# Power_Management.net
KiCad netlist of a schematic drawn in Altium Designer
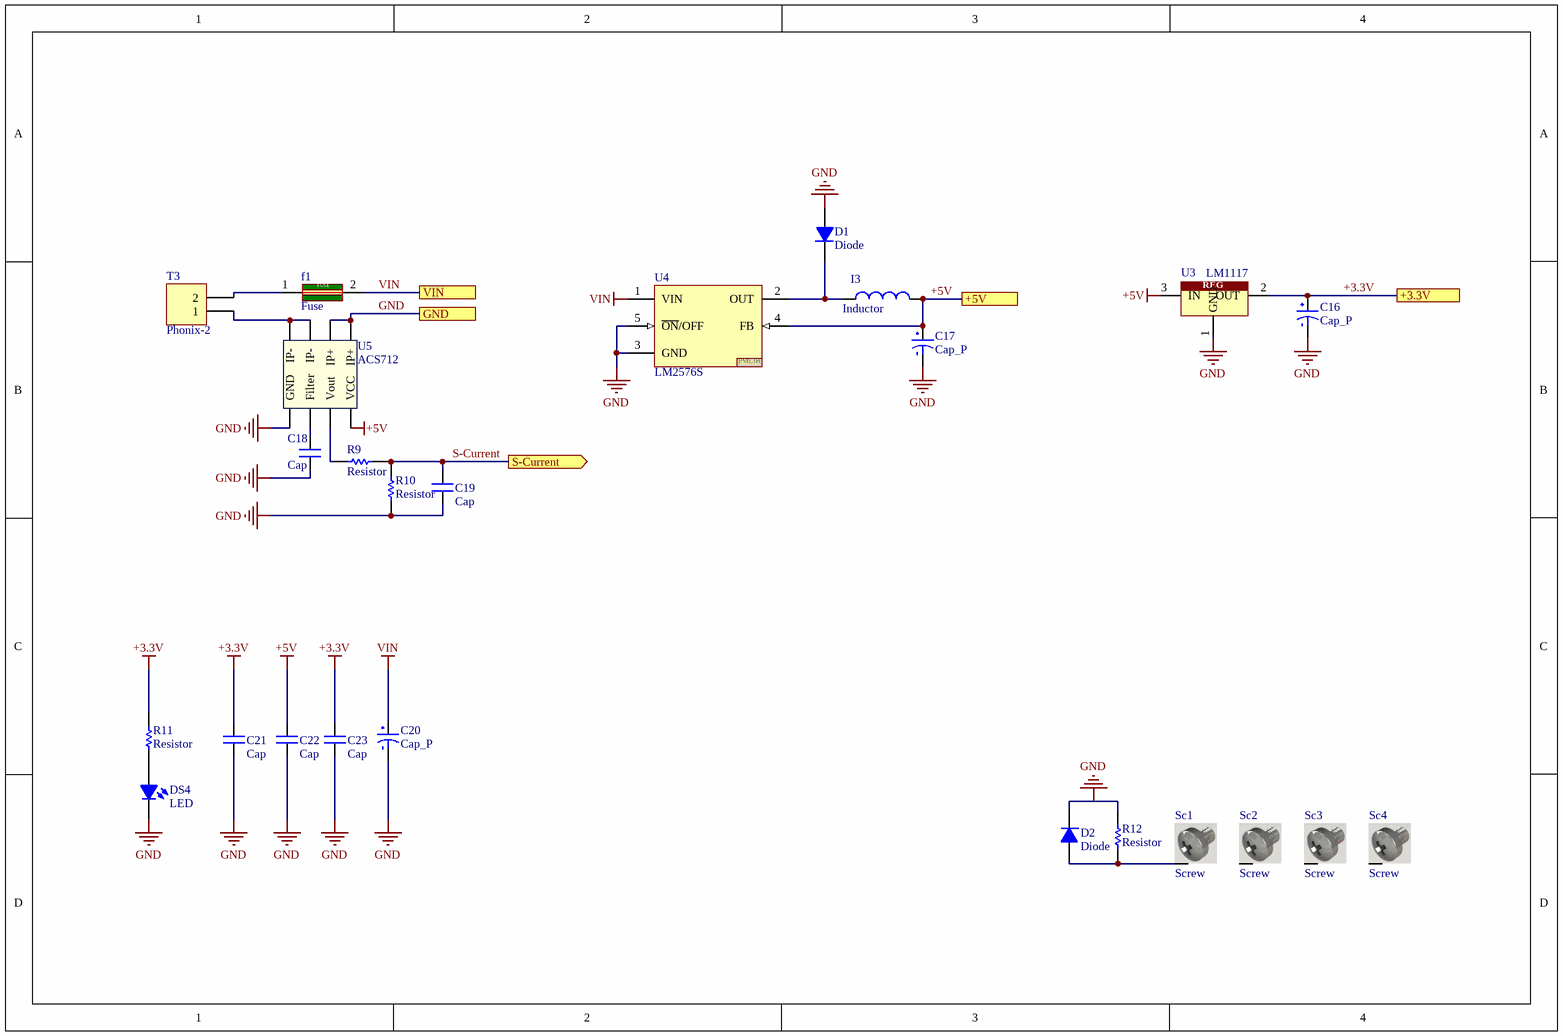
[diagram p0: Power Management.SchDoc]

(export (version "E")
  (design (tool "Eeschema 10.0.6"))
  (components
    (comp (ref "C16")
      (value "Cap_P")
      (footprint "Cap_4mm")
      (description "Polarity")
      (libsource (lib "PMLIB2020") (part "Cap_P"))
    )
    (comp (ref "C17")
      (value "Cap_P")
      (footprint "Cap_4mm")
      (description "Polarity")
      (libsource (lib "PMLIB2020") (part "Cap_P"))
    )
    (comp (ref "C18")
      (value "Cap")
      (footprint "Cap0805")
      (description "Surface mount Capacitor")
      (libsource (lib "PMLIB2020") (part "Cap"))
    )
    (comp (ref "C19")
      (value "Cap")
      (footprint "Cap0805")
      (description "Surface mount Capacitor")
      (libsource (lib "PMLIB2020") (part "Cap"))
    )
    (comp (ref "C20")
      (value "Cap_P")
      (footprint "Cap_5mm")
      (description "Polarity")
      (libsource (lib "PMLIB2020") (part "Cap_P"))
    )
    (comp (ref "C21")
      (value "Cap")
      (footprint "Cap0805")
      (description "Surface mount Capacitor")
      (libsource (lib "PMLIB2020") (part "Cap"))
    )
    (comp (ref "C22")
      (value "Cap")
      (footprint "Cap0805")
      (description "Surface mount Capacitor")
      (libsource (lib "PMLIB2020") (part "Cap"))
    )
    (comp (ref "C23")
      (value "Cap")
      (footprint "Cap0805")
      (description "Surface mount Capacitor")
      (libsource (lib "PMLIB2020") (part "Cap"))
    )
    (comp (ref "D1") (value "Diode") (footprint "Diod-1A-SMD") (libsource (lib "PMLIB2020") (part "Diode")))
    (comp (ref "D2") (value "Diode") (footprint "Diod-1A-SMD") (libsource (lib "PMLIB2020") (part "Diode")))
    (comp (ref "DS4") (value "LED") (footprint "Led0805") (libsource (lib "PMLIB2020") (part "LED")))
    (comp (ref "f1") (value "Fuse") (footprint "1206") (libsource (lib "PMLIB2020") (part "Fuse")))
    (comp (ref "I3")
      (value "Inductor")
      (footprint "Indicator_SMD")
      (description "Indicator")
      (libsource (lib "PMLIB2020") (part "Inductor"))
    )
    (comp (ref "R9") (value "Resistor") (footprint "R0805") (libsource (lib "PMLIB2020") (part "Resistor")))
    (comp (ref "R10") (value "Resistor") (footprint "R0805") (libsource (lib "PMLIB2020") (part "Resistor")))
    (comp (ref "R11") (value "Resistor") (footprint "R0805") (libsource (lib "PMLIB2020") (part "Resistor")))
    (comp (ref "R12") (value "Resistor") (footprint "0603") (libsource (lib "PMLIB2020") (part "Resistor")))
    (comp (ref "Sc1")
      (value "Screw")
      (footprint "Screw")
      (description "Screw 3mm")
      (libsource (lib "PMLIB2020") (part "Screw"))
    )
    (comp (ref "Sc2")
      (value "Screw")
      (footprint "Screw")
      (description "Screw 3mm")
      (libsource (lib "PMLIB2020") (part "Screw"))
    )
    (comp (ref "Sc3")
      (value "Screw")
      (footprint "Screw")
      (description "Screw 3mm")
      (libsource (lib "PMLIB2020") (part "Screw"))
    )
    (comp (ref "Sc4")
      (value "Screw")
      (footprint "Screw")
      (description "Screw 3mm")
      (libsource (lib "PMLIB2020") (part "Screw"))
    )
    (comp (ref "T3")
      (value "Phonix-2")
      (footprint "Phonix-2")
      (description "Connector")
      (libsource (lib "PMLIB2020") (part "Phonix-2"))
    )
    (comp (ref "U3")
      (value "LM1117")
      (footprint "DPACK")
      (description "Regulator")
      (libsource (lib "PMLIB2020") (part "LM1117"))
    )
    (comp (ref "U4")
      (value "LM2576S")
      (footprint "LM2576S")
      (description "Regulator")
      (libsource (lib "PMLIB2020") (part "LM2576S"))
    )
    (comp (ref "U5")
      (value "ACS712")
      (footprint "SOP8")
      (description "Hall effect Current Sensor")
      (libsource (lib "PMLIB2020") (part "ACS712"))
    )
  )
  (nets
    (net (code "1") (name "+3.3V") (class "Default")
      (node (ref "C16") (pin "2") (pinfunction "2_2") (pintype "passive"))
      (node (ref "C21") (pin "2") (pinfunction "2_2") (pintype "passive"))
      (node (ref "C23") (pin "2") (pinfunction "2_2") (pintype "passive"))
      (node (ref "R11") (pin "1") (pinfunction "1_1") (pintype "passive"))
      (node (ref "U3") (pin "2") (pinfunction "OUT_2") (pintype "passive"))
    )
    (net (code "2") (name "+5V") (class "Default")
      (node (ref "C17") (pin "2") (pinfunction "2_2") (pintype "passive"))
      (node (ref "C22") (pin "2") (pinfunction "2_2") (pintype "passive"))
      (node (ref "I3") (pin "2") (pinfunction "2_2") (pintype "passive"))
      (node (ref "U3") (pin "3") (pinfunction "IN_3") (pintype "passive"))
      (node (ref "U4") (pin "4") (pinfunction "FB_4") (pintype "input"))
      (node (ref "U5") (pin "8") (pinfunction "VCC_8") (pintype "passive"))
    )
    (net (code "3") (name "/S-Current") (class "Default")
      (node (ref "C19") (pin "2") (pinfunction "2_2") (pintype "passive"))
      (node (ref "R10") (pin "1") (pinfunction "1_1") (pintype "passive"))
      (node (ref "R9") (pin "1") (pinfunction "1_1") (pintype "passive"))
    )
    (net (code "4") (name "GND") (class "Default")
      (node (ref "C16") (pin "1") (pinfunction "1_1") (pintype "passive"))
      (node (ref "C17") (pin "1") (pinfunction "1_1") (pintype "passive"))
      (node (ref "C18") (pin "1") (pinfunction "1_1") (pintype "passive"))
      (node (ref "C19") (pin "1") (pinfunction "1_1") (pintype "passive"))
      (node (ref "C20") (pin "1") (pinfunction "1_1") (pintype "passive"))
      (node (ref "C21") (pin "1") (pinfunction "1_1") (pintype "passive"))
      (node (ref "C22") (pin "1") (pinfunction "1_1") (pintype "passive"))
      (node (ref "C23") (pin "1") (pinfunction "1_1") (pintype "passive"))
      (node (ref "D1") (pin "A") (pinfunction "A_A") (pintype "passive"))
      (node (ref "D2") (pin "K") (pinfunction "K_K") (pintype "passive"))
      (node (ref "DS4") (pin "K") (pinfunction "K_K") (pintype "passive"))
      (node (ref "R10") (pin "2") (pinfunction "2_2") (pintype "passive"))
      (node (ref "R12") (pin "1") (pinfunction "1_1") (pintype "passive"))
      (node (ref "U3") (pin "1") (pinfunction "GND_1") (pintype "passive"))
      (node (ref "U4") (pin "3") (pinfunction "GND_3") (pintype "power_in"))
      (node (ref "U4") (pin "5") (pinfunction "~{ON}/OFF_5") (pintype "input"))
      (node (ref "U5") (pin "1") (pinfunction "IP+_1") (pintype "passive"))
      (node (ref "U5") (pin "2") (pinfunction "IP+_2") (pintype "passive"))
      (node (ref "U5") (pin "5") (pinfunction "GND_5") (pintype "passive"))
    )
    (net (code "5") (name "Net-(D2-PadA)") (class "Default")
      (node (ref "D2") (pin "A") (pinfunction "A_A") (pintype "passive"))
      (node (ref "R12") (pin "2") (pinfunction "2_2") (pintype "passive"))
      (node (ref "Sc1") (pin "S") (pinfunction "S_S") (pintype "passive"))
    )
    (net (code "6") (name "Net-(DS4-PadA)") (class "Default")
      (node (ref "DS4") (pin "A") (pinfunction "A_A") (pintype "passive"))
      (node (ref "R11") (pin "2") (pinfunction "2_2") (pintype "passive"))
    )
    (net (code "7") (name "Net-(T3-Pad1)") (class "Default")
      (node (ref "T3") (pin "1") (pinfunction "1_1") (pintype "passive"))
      (node (ref "U5") (pin "3") (pinfunction "IP-_3") (pintype "passive"))
      (node (ref "U5") (pin "4") (pinfunction "IP-_4") (pintype "passive"))
    )
    (net (code "8") (name "Net-(U4-OUT)") (class "Default")
      (node (ref "D1") (pin "K") (pinfunction "K_K") (pintype "passive"))
      (node (ref "I3") (pin "1") (pinfunction "1_1") (pintype "passive"))
      (node (ref "U4") (pin "2") (pinfunction "OUT_2") (pintype "power_in"))
    )
    (net (code "9") (name "Net-(U5-Filter)") (class "Default")
      (node (ref "C18") (pin "2") (pinfunction "2_2") (pintype "passive"))
      (node (ref "U5") (pin "6") (pinfunction "Filter_6") (pintype "passive"))
    )
    (net (code "10") (name "Net-(U5-Vout)") (class "Default")
      (node (ref "R9") (pin "2") (pinfunction "2_2") (pintype "passive"))
      (node (ref "U5") (pin "7") (pinfunction "Vout_7") (pintype "passive"))
    )
    (net (code "11") (name "Net-(f1-IN)") (class "Default")
      (node (ref "T3") (pin "2") (pinfunction "2_2") (pintype "passive"))
      (node (ref "f1") (pin "1") (pinfunction "IN_1") (pintype "passive"))
    )
    (net (code "12") (name "VIN") (class "Default")
      (node (ref "C20") (pin "2") (pinfunction "2_2") (pintype "passive"))
      (node (ref "U4") (pin "1") (pinfunction "VIN_1") (pintype "power_in"))
      (node (ref "f1") (pin "2") (pinfunction "OUT_2") (pintype "passive"))
    )
    (net (code "13") (name "unconnected-(Sc2-PadS)") (class "Default")
      (node (ref "Sc2") (pin "S") (pinfunction "S_S") (pintype "passive"))
    )
    (net (code "14") (name "unconnected-(Sc3-PadS)") (class "Default")
      (node (ref "Sc3") (pin "S") (pinfunction "S_S") (pintype "passive"))
    )
    (net (code "15") (name "unconnected-(Sc4-PadS)") (class "Default")
      (node (ref "Sc4") (pin "S") (pinfunction "S_S") (pintype "passive"))
    )
  )
)
